# ziffy_board.net
KiCad netlist of a schematic drawn in EAGLE
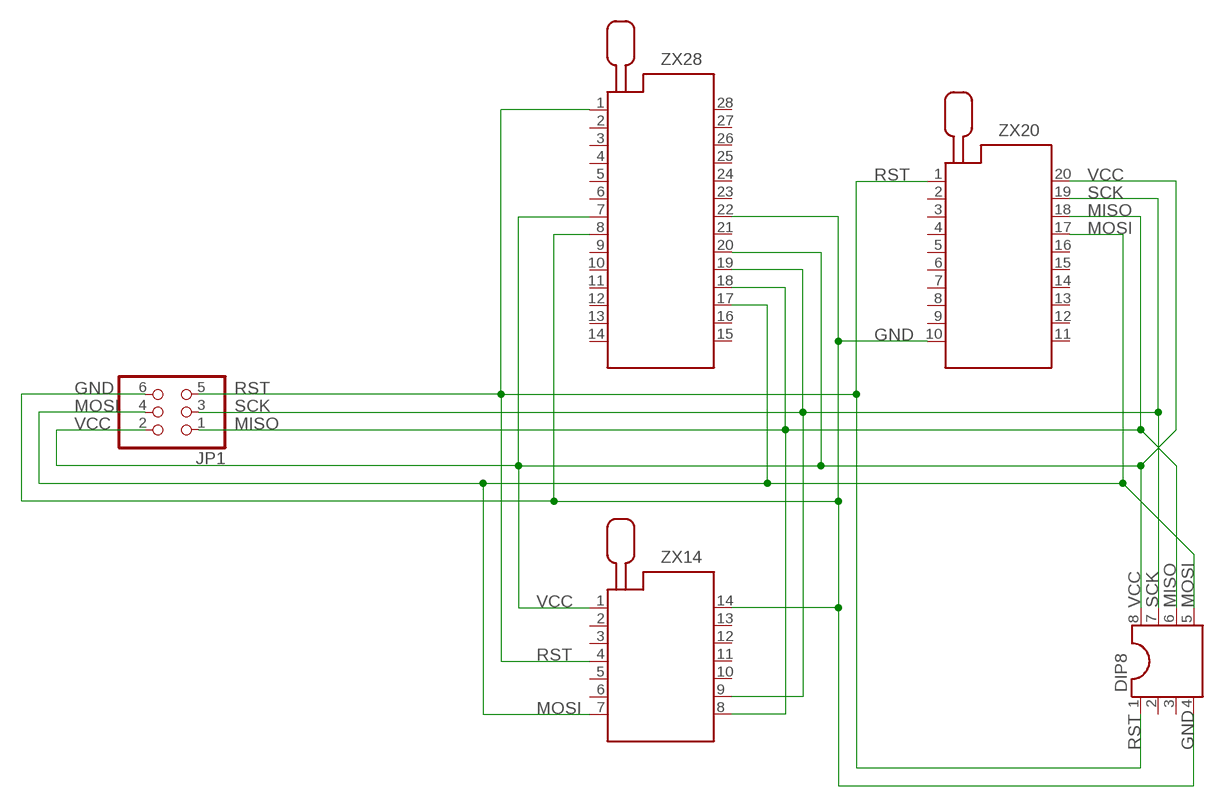
[diagram p0: schematic, sheet 1]

(export (version "E")
  (design (tool "Eeschema 10.0.6"))
  (components
    (comp (ref "DIP8")
      (value "DIL8S")
      (footprint "eagle-import:SOCKET-08")
      (libsource (lib "eagle-import") (part "DIL8S"))
    )
    (comp (ref "JP1")
      (value "PINHD-2X3")
      (footprint "eagle-import:2X03")
      (libsource (lib "eagle-import") (part "PINHD-2X3"))
    )
    (comp (ref "ZX14")
      (value "214-3339-00-0602J")
      (footprint "eagle-import:214-3339-00-0602J")
      (fields (field (name "MF") "3M"))
      (libsource (lib "eagle-import") (part "214-3339-00-0602J"))
    )
    (comp (ref "ZX20")
      (value "220-3342-00-0602J")
      (footprint "eagle-import:220-3342-00-0602J")
      (fields (field (name "MF") "3M"))
      (libsource (lib "eagle-import") (part "220-3342-00-0602J"))
    )
    (comp (ref "ZX28")
      (value "228-4817-00-0602J")
      (footprint "eagle-import:228-4817-00-0602J")
      (fields (field (name "MF") "3M"))
      (libsource (lib "eagle-import") (part "228-?00-0602J4817-"))
    )
  )
  (nets
    (net (code "1") (name "/GND") (class "Default")
      (node (ref "DIP8") (pin "4") (pinfunction "4_4") (pintype "passive"))
      (node (ref "JP1") (pin "6") (pinfunction "6_6") (pintype "passive"))
      (node (ref "ZX14") (pin "14") (pinfunction "14_14") (pintype "passive"))
      (node (ref "ZX20") (pin "10") (pinfunction "10_10") (pintype "passive"))
      (node (ref "ZX28") (pin "22") (pinfunction "22_22") (pintype "passive"))
      (node (ref "ZX28") (pin "8") (pinfunction "8_8") (pintype "passive"))
    )
    (net (code "2") (name "/MISO") (class "Default")
      (node (ref "DIP8") (pin "6") (pinfunction "6_6") (pintype "passive"))
      (node (ref "JP1") (pin "1") (pinfunction "1_1") (pintype "passive"))
      (node (ref "ZX14") (pin "8") (pinfunction "8_8") (pintype "passive"))
      (node (ref "ZX20") (pin "18") (pinfunction "18_18") (pintype "passive"))
      (node (ref "ZX28") (pin "18") (pinfunction "18_18") (pintype "passive"))
    )
    (net (code "3") (name "/MOSI") (class "Default")
      (node (ref "DIP8") (pin "5") (pinfunction "5_5") (pintype "passive"))
      (node (ref "JP1") (pin "4") (pinfunction "4_4") (pintype "passive"))
      (node (ref "ZX14") (pin "7") (pinfunction "7_7") (pintype "passive"))
      (node (ref "ZX20") (pin "17") (pinfunction "17_17") (pintype "passive"))
      (node (ref "ZX28") (pin "17") (pinfunction "17_17") (pintype "passive"))
    )
    (net (code "4") (name "/RST") (class "Default")
      (node (ref "DIP8") (pin "1") (pinfunction "1_1") (pintype "passive"))
      (node (ref "JP1") (pin "5") (pinfunction "5_5") (pintype "passive"))
      (node (ref "ZX14") (pin "4") (pinfunction "4_4") (pintype "passive"))
      (node (ref "ZX20") (pin "1") (pinfunction "1_1") (pintype "passive"))
      (node (ref "ZX28") (pin "1") (pinfunction "1_1") (pintype "passive"))
    )
    (net (code "5") (name "/SCK") (class "Default")
      (node (ref "DIP8") (pin "7") (pinfunction "7_7") (pintype "passive"))
      (node (ref "JP1") (pin "3") (pinfunction "3_3") (pintype "passive"))
      (node (ref "ZX14") (pin "9") (pinfunction "9_9") (pintype "passive"))
      (node (ref "ZX20") (pin "19") (pinfunction "19_19") (pintype "passive"))
      (node (ref "ZX28") (pin "19") (pinfunction "19_19") (pintype "passive"))
    )
    (net (code "6") (name "/VCC") (class "Default")
      (node (ref "DIP8") (pin "8") (pinfunction "8_8") (pintype "passive"))
      (node (ref "JP1") (pin "2") (pinfunction "2_2") (pintype "passive"))
      (node (ref "ZX14") (pin "1") (pinfunction "1_1") (pintype "passive"))
      (node (ref "ZX20") (pin "20") (pinfunction "20_20") (pintype "passive"))
      (node (ref "ZX28") (pin "20") (pinfunction "20_20") (pintype "passive"))
      (node (ref "ZX28") (pin "7") (pinfunction "7_7") (pintype "passive"))
    )
    (net (code "7") (name "unconnected-(DIP8-Pad2)") (class "Default")
      (node (ref "DIP8") (pin "2") (pinfunction "2_2") (pintype "passive"))
    )
    (net (code "8") (name "unconnected-(DIP8-Pad3)") (class "Default")
      (node (ref "DIP8") (pin "3") (pinfunction "3_3") (pintype "passive"))
    )
    (net (code "9") (name "unconnected-(ZX14-Pad2)") (class "Default")
      (node (ref "ZX14") (pin "2") (pinfunction "2_2") (pintype "passive"))
    )
    (net (code "10") (name "unconnected-(ZX14-Pad3)") (class "Default")
      (node (ref "ZX14") (pin "3") (pinfunction "3_3") (pintype "passive"))
    )
    (net (code "11") (name "unconnected-(ZX14-Pad5)") (class "Default")
      (node (ref "ZX14") (pin "5") (pinfunction "5_5") (pintype "passive"))
    )
    (net (code "12") (name "unconnected-(ZX14-Pad6)") (class "Default")
      (node (ref "ZX14") (pin "6") (pinfunction "6_6") (pintype "passive"))
    )
    (net (code "13") (name "unconnected-(ZX14-Pad10)") (class "Default")
      (node (ref "ZX14") (pin "10") (pinfunction "10_10") (pintype "passive"))
    )
    (net (code "14") (name "unconnected-(ZX14-Pad11)") (class "Default")
      (node (ref "ZX14") (pin "11") (pinfunction "11_11") (pintype "passive"))
    )
    (net (code "15") (name "unconnected-(ZX14-Pad12)") (class "Default")
      (node (ref "ZX14") (pin "12") (pinfunction "12_12") (pintype "passive"))
    )
    (net (code "16") (name "unconnected-(ZX14-Pad13)") (class "Default")
      (node (ref "ZX14") (pin "13") (pinfunction "13_13") (pintype "passive"))
    )
    (net (code "17") (name "unconnected-(ZX20-Pad2)") (class "Default")
      (node (ref "ZX20") (pin "2") (pinfunction "2_2") (pintype "passive"))
    )
    (net (code "18") (name "unconnected-(ZX20-Pad3)") (class "Default")
      (node (ref "ZX20") (pin "3") (pinfunction "3_3") (pintype "passive"))
    )
    (net (code "19") (name "unconnected-(ZX20-Pad4)") (class "Default")
      (node (ref "ZX20") (pin "4") (pinfunction "4_4") (pintype "passive"))
    )
    (net (code "20") (name "unconnected-(ZX20-Pad5)") (class "Default")
      (node (ref "ZX20") (pin "5") (pinfunction "5_5") (pintype "passive"))
    )
    (net (code "21") (name "unconnected-(ZX20-Pad6)") (class "Default")
      (node (ref "ZX20") (pin "6") (pinfunction "6_6") (pintype "passive"))
    )
    (net (code "22") (name "unconnected-(ZX20-Pad7)") (class "Default")
      (node (ref "ZX20") (pin "7") (pinfunction "7_7") (pintype "passive"))
    )
    (net (code "23") (name "unconnected-(ZX20-Pad8)") (class "Default")
      (node (ref "ZX20") (pin "8") (pinfunction "8_8") (pintype "passive"))
    )
    (net (code "24") (name "unconnected-(ZX20-Pad9)") (class "Default")
      (node (ref "ZX20") (pin "9") (pinfunction "9_9") (pintype "passive"))
    )
    (net (code "25") (name "unconnected-(ZX20-Pad11)") (class "Default")
      (node (ref "ZX20") (pin "11") (pinfunction "11_11") (pintype "passive"))
    )
    (net (code "26") (name "unconnected-(ZX20-Pad12)") (class "Default")
      (node (ref "ZX20") (pin "12") (pinfunction "12_12") (pintype "passive"))
    )
    (net (code "27") (name "unconnected-(ZX20-Pad13)") (class "Default")
      (node (ref "ZX20") (pin "13") (pinfunction "13_13") (pintype "passive"))
    )
    (net (code "28") (name "unconnected-(ZX20-Pad14)") (class "Default")
      (node (ref "ZX20") (pin "14") (pinfunction "14_14") (pintype "passive"))
    )
    (net (code "29") (name "unconnected-(ZX20-Pad15)") (class "Default")
      (node (ref "ZX20") (pin "15") (pinfunction "15_15") (pintype "passive"))
    )
    (net (code "30") (name "unconnected-(ZX20-Pad16)") (class "Default")
      (node (ref "ZX20") (pin "16") (pinfunction "16_16") (pintype "passive"))
    )
    (net (code "31") (name "unconnected-(ZX28-Pad2)") (class "Default")
      (node (ref "ZX28") (pin "2") (pinfunction "2_2") (pintype "passive"))
    )
    (net (code "32") (name "unconnected-(ZX28-Pad3)") (class "Default")
      (node (ref "ZX28") (pin "3") (pinfunction "3_3") (pintype "passive"))
    )
    (net (code "33") (name "unconnected-(ZX28-Pad4)") (class "Default")
      (node (ref "ZX28") (pin "4") (pinfunction "4_4") (pintype "passive"))
    )
    (net (code "34") (name "unconnected-(ZX28-Pad5)") (class "Default")
      (node (ref "ZX28") (pin "5") (pinfunction "5_5") (pintype "passive"))
    )
    (net (code "35") (name "unconnected-(ZX28-Pad6)") (class "Default")
      (node (ref "ZX28") (pin "6") (pinfunction "6_6") (pintype "passive"))
    )
    (net (code "36") (name "unconnected-(ZX28-Pad9)") (class "Default")
      (node (ref "ZX28") (pin "9") (pinfunction "9_9") (pintype "passive"))
    )
    (net (code "37") (name "unconnected-(ZX28-Pad10)") (class "Default")
      (node (ref "ZX28") (pin "10") (pinfunction "10_10") (pintype "passive"))
    )
    (net (code "38") (name "unconnected-(ZX28-Pad11)") (class "Default")
      (node (ref "ZX28") (pin "11") (pinfunction "11_11") (pintype "passive"))
    )
    (net (code "39") (name "unconnected-(ZX28-Pad12)") (class "Default")
      (node (ref "ZX28") (pin "12") (pinfunction "12_12") (pintype "passive"))
    )
    (net (code "40") (name "unconnected-(ZX28-Pad13)") (class "Default")
      (node (ref "ZX28") (pin "13") (pinfunction "13_13") (pintype "passive"))
    )
    (net (code "41") (name "unconnected-(ZX28-Pad14)") (class "Default")
      (node (ref "ZX28") (pin "14") (pinfunction "14_14") (pintype "passive"))
    )
    (net (code "42") (name "unconnected-(ZX28-Pad15)") (class "Default")
      (node (ref "ZX28") (pin "15") (pinfunction "15_15") (pintype "passive"))
    )
    (net (code "43") (name "unconnected-(ZX28-Pad16)") (class "Default")
      (node (ref "ZX28") (pin "16") (pinfunction "16_16") (pintype "passive"))
    )
    (net (code "44") (name "unconnected-(ZX28-Pad21)") (class "Default")
      (node (ref "ZX28") (pin "21") (pinfunction "21_21") (pintype "passive"))
    )
    (net (code "45") (name "unconnected-(ZX28-Pad23)") (class "Default")
      (node (ref "ZX28") (pin "23") (pinfunction "23_23") (pintype "passive"))
    )
    (net (code "46") (name "unconnected-(ZX28-Pad24)") (class "Default")
      (node (ref "ZX28") (pin "24") (pinfunction "24_24") (pintype "passive"))
    )
    (net (code "47") (name "unconnected-(ZX28-Pad25)") (class "Default")
      (node (ref "ZX28") (pin "25") (pinfunction "25_25") (pintype "passive"))
    )
    (net (code "48") (name "unconnected-(ZX28-Pad26)") (class "Default")
      (node (ref "ZX28") (pin "26") (pinfunction "26_26") (pintype "passive"))
    )
    (net (code "49") (name "unconnected-(ZX28-Pad27)") (class "Default")
      (node (ref "ZX28") (pin "27") (pinfunction "27_27") (pintype "passive"))
    )
    (net (code "50") (name "unconnected-(ZX28-Pad28)") (class "Default")
      (node (ref "ZX28") (pin "28") (pinfunction "28_28") (pintype "passive"))
    )
  )
)
